# quad_nand_gate_CMOS.net
KiCad netlist of a schematic drawn in EAGLE
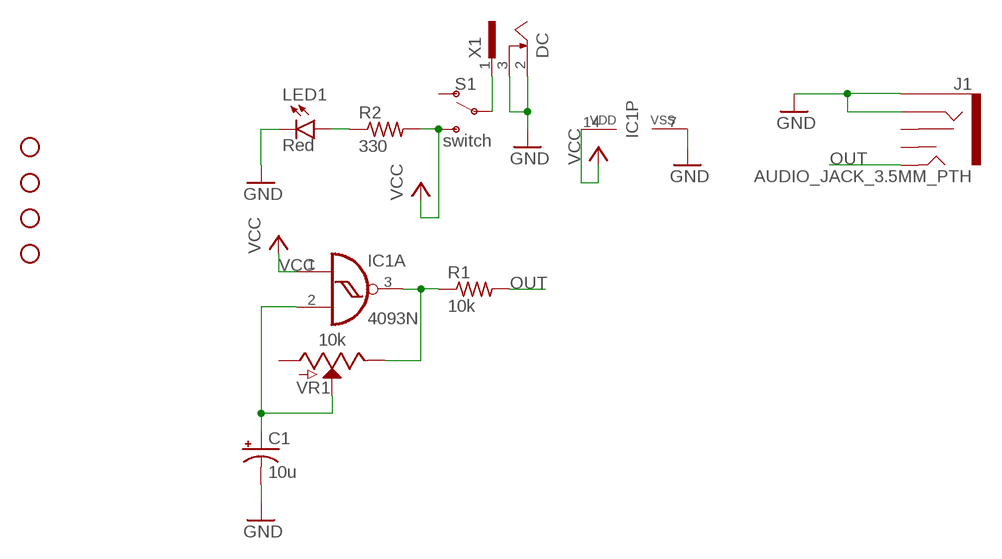
[diagram p0: schematic, sheet 1]

(export (version "E")
  (design (tool "Eeschema 10.0.6"))
  (components
    (comp (ref "C1")
      (value "10u")
      (footprint "eagle-import:E2,5-5")
      (libsource (lib "eagle-import") (part "CPOL-USE2.5-5"))
    )
    (comp (ref "H1")
      (value "STAND-OFF")
      (footprint "eagle-import:STAND-OFF")
      (libsource (lib "eagle-import") (part "STAND-OFF"))
    )
    (comp (ref "H2")
      (value "STAND-OFF")
      (footprint "eagle-import:STAND-OFF")
      (libsource (lib "eagle-import") (part "STAND-OFF"))
    )
    (comp (ref "H3")
      (value "STAND-OFF")
      (footprint "eagle-import:STAND-OFF")
      (libsource (lib "eagle-import") (part "STAND-OFF"))
    )
    (comp (ref "H4")
      (value "STAND-OFF")
      (footprint "eagle-import:STAND-OFF")
      (libsource (lib "eagle-import") (part "STAND-OFF"))
    )
    (comp (ref "IC1")
      (value "4093N")
      (footprint "eagle-import:DIL14")
      (libsource (lib "eagle-import") (part "4093N"))
    )
    (comp (ref "J1")
      (value "AUDIO_JACK_3.5MM_PTH")
      (footprint "eagle-import:AUDIO-JACK")
      (libsource (lib "eagle-import") (part "AUDIO_JACK_3.5MM_PTH"))
    )
    (comp (ref "LED1")
      (value "Red")
      (footprint "eagle-import:LED5MM")
      (libsource (lib "eagle-import") (part "LED5MM"))
    )
    (comp (ref "R1")
      (value "10k")
      (footprint "eagle-import:0204_5_66PADS")
      (libsource (lib "eagle-import") (part "R-US_0204/5"))
    )
    (comp (ref "R2")
      (value "330")
      (footprint "eagle-import:0204_5_66PADS")
      (libsource (lib "eagle-import") (part "R-US_0204/5"))
    )
    (comp (ref "S1")
      (value "switch")
      (footprint "eagle-import:SWITCH_SPDT_PTH_11.6X4.0MM_LOCK")
      (libsource (lib "eagle-import") (part "SWITCH-SPDT-PTH-11.6X4.0MM-LOCK"))
    )
    (comp (ref "VR1")
      (value "10k")
      (footprint "eagle-import:POT-PTH-ALPS")
      (libsource (lib "eagle-import") (part "POTENTIOMETER-PTH-9MM-1/20W-20%"))
    )
    (comp (ref "X1")
      (value "DC")
      (footprint "eagle-import:SCD-014-A")
      (libsource (lib "eagle-import") (part "SCD-014A"))
    )
  )
  (nets
    (net (code "1") (name "/OUT") (class "Default")
      (node (ref "J1") (pin "TIP") (pinfunction "TIP_TIP") (pintype "bidirectional"))
      (node (ref "R1") (pin "2") (pinfunction "2_2") (pintype "passive"))
    )
    (net (code "2") (name "GND") (class "Default")
      (node (ref "C1") (pin "-") (pinfunction "-_-") (pintype "passive"))
      (node (ref "IC1") (pin "7") (pinfunction "VSS_7") (pintype "power_in"))
      (node (ref "J1") (pin "RING") (pinfunction "RING_RING") (pintype "bidirectional"))
      (node (ref "J1") (pin "SLEEVE") (pinfunction "SLEEVE_SLEEVE") (pintype "bidirectional"))
      (node (ref "LED1") (pin "K") (pinfunction "C_K") (pintype "passive"))
      (node (ref "X1") (pin "2") (pinfunction "2_2") (pintype "passive"))
      (node (ref "X1") (pin "3") (pinfunction "3_3") (pintype "passive"))
    )
    (net (code "3") (name "Net-(IC1A-I1)") (class "Default")
      (node (ref "C1") (pin "+") (pinfunction "+_+") (pintype "passive"))
      (node (ref "IC1") (pin "2") (pinfunction "I1_2") (pintype "input"))
      (node (ref "VR1") (pin "P$2") (pinfunction "S_P$2") (pintype "passive"))
    )
    (net (code "4") (name "Net-(IC1A-O)") (class "Default")
      (node (ref "IC1") (pin "3") (pinfunction "O_3") (pintype "output"))
      (node (ref "R1") (pin "1") (pinfunction "1_1") (pintype "passive"))
      (node (ref "VR1") (pin "P$1") (pinfunction "E_P$1") (pintype "passive"))
    )
    (net (code "5") (name "Net-(LED1-PadA)") (class "Default")
      (node (ref "LED1") (pin "A") (pinfunction "A_A") (pintype "passive"))
      (node (ref "R2") (pin "1") (pinfunction "1_1") (pintype "passive"))
    )
    (net (code "6") (name "Net-(S1-P)") (class "Default")
      (node (ref "S1") (pin "2") (pinfunction "P_2") (pintype "passive"))
      (node (ref "X1") (pin "1") (pinfunction "1_1") (pintype "passive"))
    )
    (net (code "7") (name "VCC") (class "Default")
      (node (ref "IC1") (pin "1") (pinfunction "I0_1") (pintype "input"))
      (node (ref "IC1") (pin "14") (pinfunction "VDD_14") (pintype "power_in"))
      (node (ref "R2") (pin "2") (pinfunction "2_2") (pintype "passive"))
      (node (ref "S1") (pin "3") (pinfunction "S_3") (pintype "passive"))
    )
    (net (code "8") (name "unconnected-(J1-PadRSH)") (class "Default")
      (node (ref "J1") (pin "RSH") (pinfunction "RSH_RSH") (pintype "bidirectional"))
    )
    (net (code "9") (name "unconnected-(J1-PadTSH)") (class "Default")
      (node (ref "J1") (pin "TSH") (pinfunction "TSH_TSH") (pintype "bidirectional"))
    )
    (net (code "10") (name "unconnected-(S1-O-Pad1)") (class "Default")
      (node (ref "S1") (pin "1") (pinfunction "O_1") (pintype "passive"))
    )
    (net (code "11") (name "unconnected-(VR1-A-PadP$3)") (class "Default")
      (node (ref "VR1") (pin "P$3") (pinfunction "A_P$3") (pintype "passive"))
    )
  )
)
